# 1_8_4_-_-V2_0-2022_05_13.net
KiCad netlist of a schematic drawn in Altium Designer
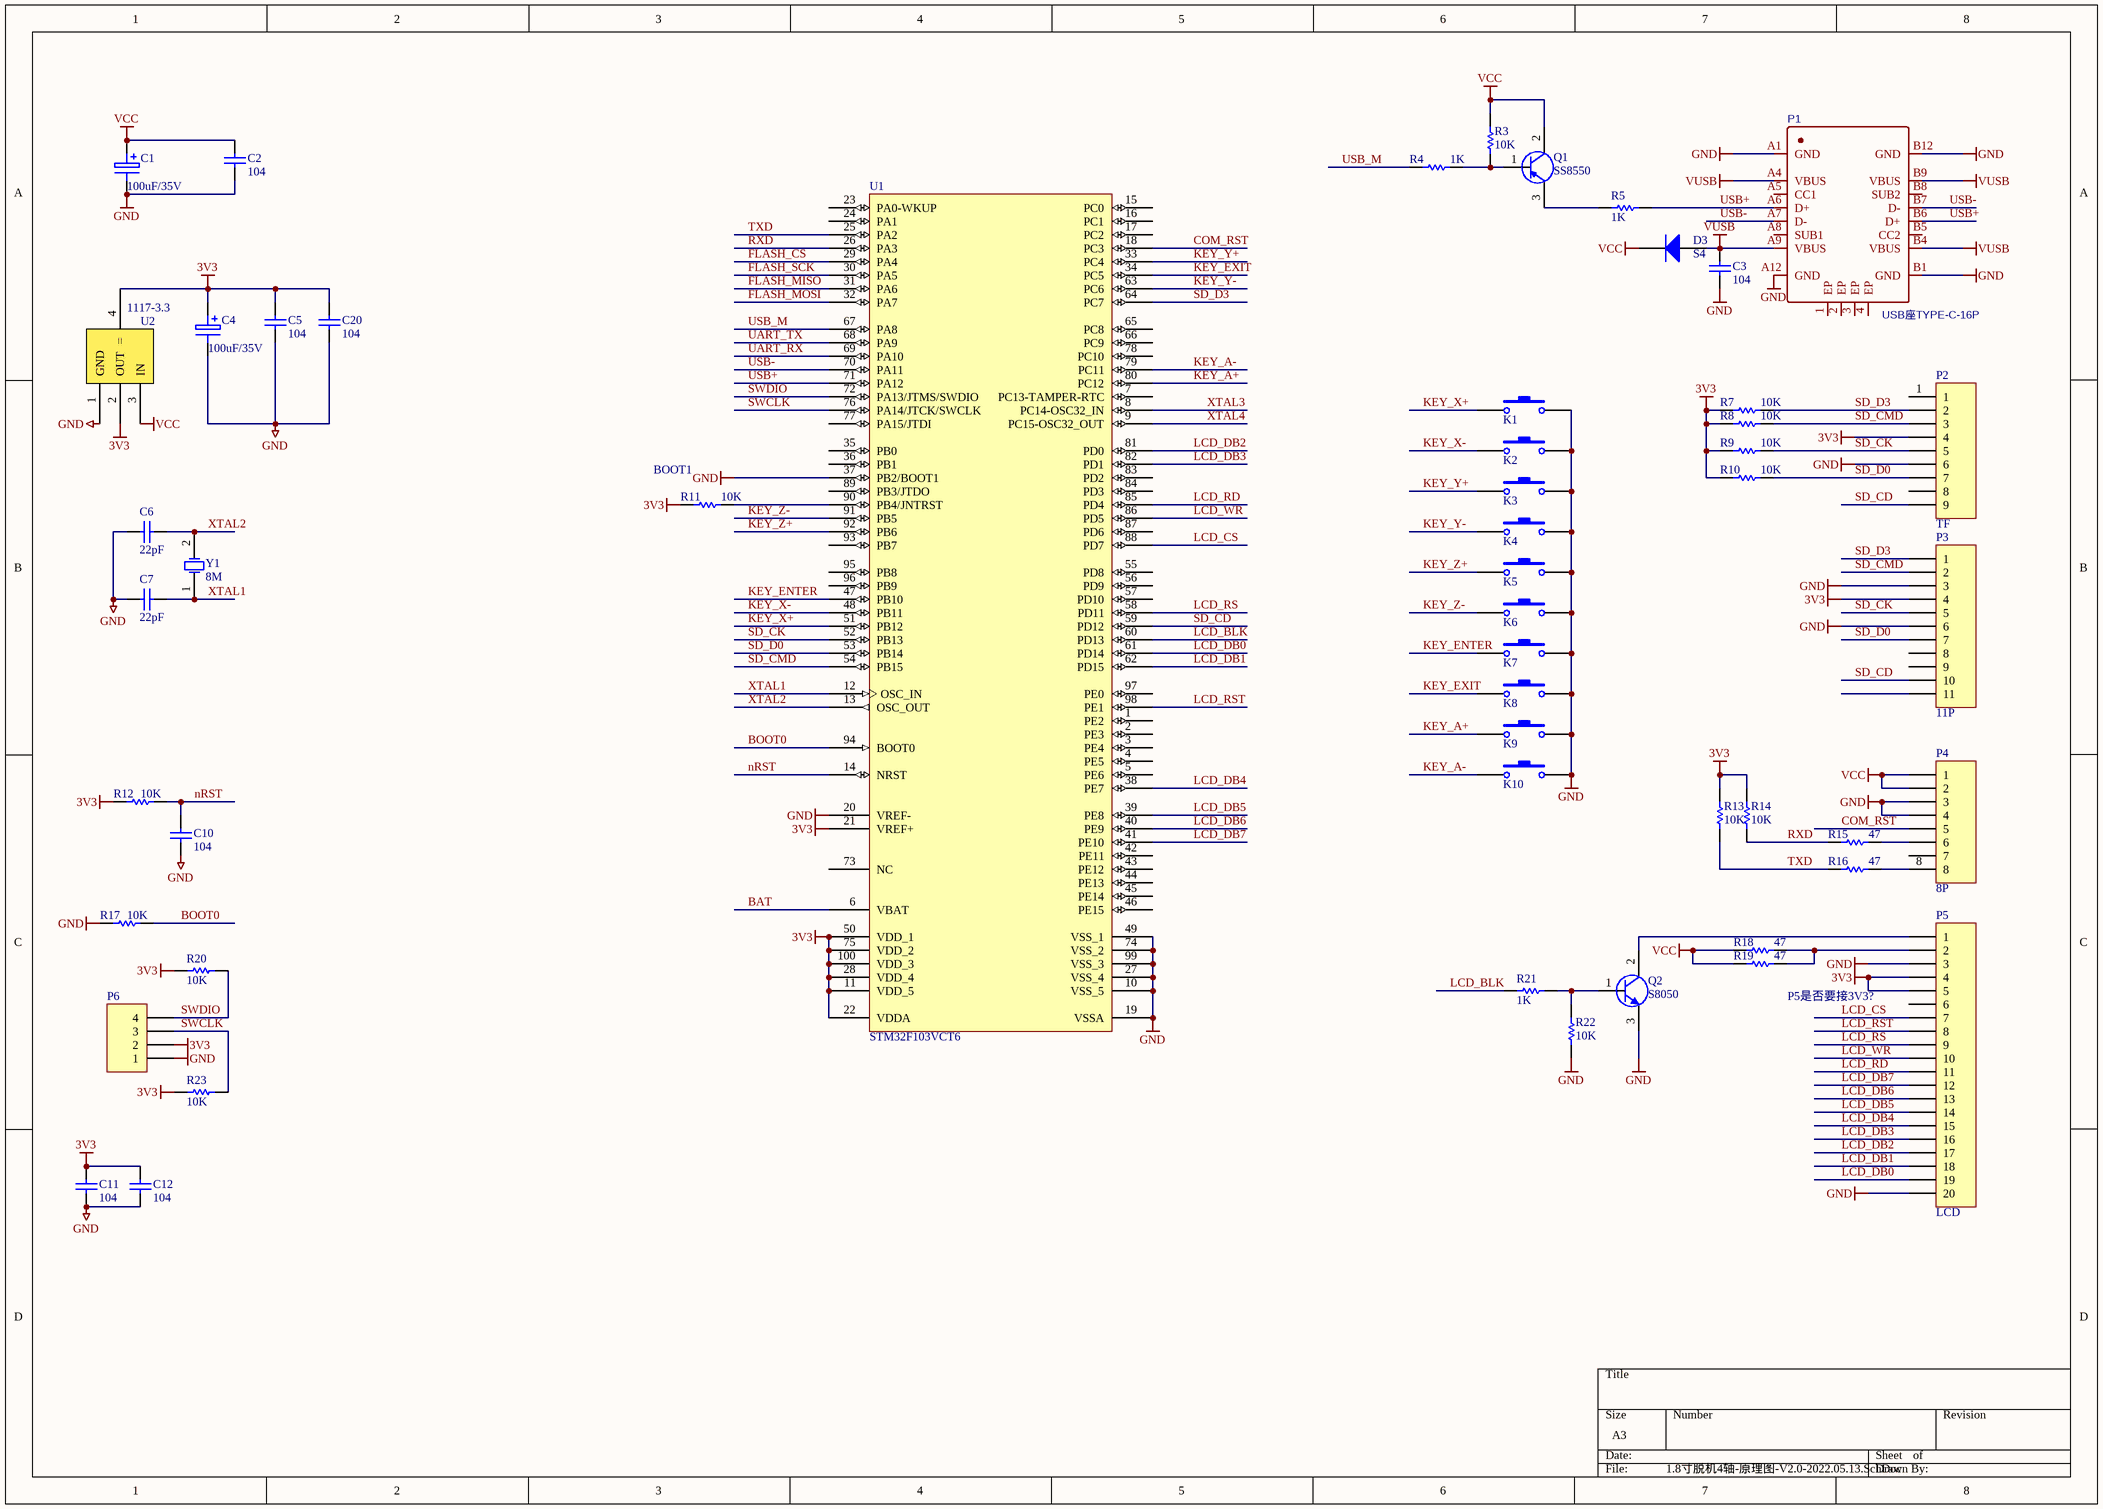
[diagram p0: 1.8寸脱机4轴-原理图-V2.0-2022.05.13.SchDoc]

(export (version "E")
  (design (tool "Eeschema 10.0.6"))
  (components
    (comp (ref "C1") (value "100uF/35V") (footprint "电解电容贴片6x6") (libsource (lib "*") (part "ELECTRO1")))
    (comp (ref "C2")
      (value "104")
      (footprint "0603C")
      (description "Capacitor (Semiconductor SIM Model)")
      (fields (field (name "PUBLISHER") "Altium Limited"))
      (libsource (lib "Miscellaneous Devices") (part "Cap Semi"))
    )
    (comp (ref "C3")
      (value "104")
      (footprint "0603C")
      (description "Capacitor (Semiconductor SIM Model)")
      (fields (field (name "PUBLISHER") "Altium Limited"))
      (libsource (lib "Miscellaneous Devices") (part "Cap Semi"))
    )
    (comp (ref "C4") (value "100uF/35V") (footprint "电解电容贴片6x6") (libsource (lib "*") (part "ELECTRO1")))
    (comp (ref "C5")
      (value "104")
      (footprint "0603C")
      (description "Capacitor (Semiconductor SIM Model)")
      (fields (field (name "PUBLISHER") "Altium Limited"))
      (libsource (lib "Miscellaneous Devices") (part "Cap Semi"))
    )
    (comp (ref "C6")
      (value "22pF")
      (footprint "0603C")
      (description "Capacitor (Semiconductor SIM Model)")
      (fields (field (name "PUBLISHER") "Altium Limited"))
      (libsource (lib "Miscellaneous Devices") (part "Cap Semi"))
    )
    (comp (ref "C7")
      (value "22pF")
      (footprint "0603C")
      (description "Capacitor (Semiconductor SIM Model)")
      (fields (field (name "PUBLISHER") "Altium Limited"))
      (libsource (lib "Miscellaneous Devices") (part "Cap Semi"))
    )
    (comp (ref "C10")
      (value "104")
      (footprint "0603C")
      (description "Capacitor (Semiconductor SIM Model)")
      (fields (field (name "PUBLISHER") "Altium Limited"))
      (libsource (lib "Miscellaneous Devices") (part "Cap Semi"))
    )
    (comp (ref "C11") (value "104") (footprint "0603C") (libsource (lib "SCH封装库") (part "CAP")))
    (comp (ref "C12") (value "104") (footprint "0603C") (libsource (lib "SCH封装库") (part "CAP")))
    (comp (ref "C20")
      (value "104")
      (footprint "0603C")
      (description "Capacitor (Semiconductor SIM Model)")
      (fields (field (name "Comment") "106") (field (name "PUBLISHER") "Altium Limited"))
      (libsource (lib "Miscellaneous Devices") (part "Cap Semi"))
    )
    (comp (ref "D3") (value "S4") (footprint "SOD-123") (libsource (lib "SCH封装库") (part "1N4148")))
    (comp (ref "K1") (value "~") (footprint "按键6x6贴片") (libsource (lib "SCH封装库") (part "按键")))
    (comp (ref "K2") (value "~") (footprint "按键6x6贴片") (libsource (lib "SCH封装库") (part "按键")))
    (comp (ref "K3") (value "~") (footprint "按键6x6贴片") (libsource (lib "SCH封装库") (part "按键")))
    (comp (ref "K4") (value "~") (footprint "按键6x6贴片") (libsource (lib "SCH封装库") (part "按键")))
    (comp (ref "K5") (value "~") (footprint "按键6x6贴片") (libsource (lib "SCH封装库") (part "按键")))
    (comp (ref "K6") (value "~") (footprint "按键6x6贴片") (libsource (lib "SCH封装库") (part "按键")))
    (comp (ref "K7") (value "~") (footprint "按键6x6贴片") (libsource (lib "SCH封装库") (part "按键")))
    (comp (ref "K8") (value "~") (footprint "按键6x6贴片") (libsource (lib "SCH封装库") (part "按键")))
    (comp (ref "K9") (value "~") (footprint "按键6x6贴片") (libsource (lib "SCH封装库") (part "按键")))
    (comp (ref "K10") (value "~") (footprint "按键6x6贴片") (libsource (lib "SCH封装库") (part "按键")))
    (comp (ref "P1")
      (value "USB座TYPE-C-16P")
      (footprint "USB-TYPE-C-16P-全贴片")
      (fields
        (field (name "BOM_SUPPLIER PART") "C709358")
        (field (name "BOM_MANUFACTURER PART") "KH-TYPE-C-16P-T")
        (field (name "CONTRIBUTOR") "LCSC")
      )
      (libsource (lib "SCH封装库") (part "USB座TYPE-C-16P"))
    )
    (comp (ref "P2") (value "TF") (footprint "TF卡自弹式") (libsource (lib "SCH封装库") (part "9P")))
    (comp (ref "P3") (value "11P") (footprint "SD卡座自弹式") (libsource (lib "SCH封装库") (part "11P")))
    (comp (ref "P4") (value "8P") (footprint "IDC8贴片") (libsource (lib "SCH封装库") (part "8P")))
    (comp (ref "P5") (value "LCD") (footprint "显示屏1.77寸") (libsource (lib "SCH封装库") (part "20P")))
    (comp (ref "P6") (value "~") (footprint "SIP4") (libsource (lib "SCH封装库") (part "4P")))
    (comp (ref "Q1") (value "SS8550") (footprint "SOT-23") (libsource (lib "SCH封装库") (part "PNP")))
    (comp (ref "Q2")
      (value "S8050")
      (footprint "SOT-23")
      (fields (field (name "PUBLISHER") "Altium Limited"))
      (libsource (lib "SCH封装库") (part "NPN"))
    )
    (comp (ref "R3")
      (value "10K")
      (footprint "0603R")
      (description "Resistor")
      (fields (field (name "PUBLISHER") "Altium Limited"))
      (libsource (lib "SCH封装库") (part "RES"))
    )
    (comp (ref "R4")
      (value "1K")
      (footprint "0603R")
      (description "Resistor")
      (fields (field (name "PUBLISHER") "Altium Limited"))
      (libsource (lib "SCH封装库") (part "RES"))
    )
    (comp (ref "R5")
      (value "1K")
      (footprint "0603R")
      (description "Resistor")
      (fields (field (name "PUBLISHER") "Altium Limited"))
      (libsource (lib "SCH封装库") (part "RES"))
    )
    (comp (ref "R7")
      (value "10K")
      (footprint "0603R")
      (description "Resistor")
      (fields (field (name "PUBLISHER") "Altium Limited"))
      (libsource (lib "SCH封装库") (part "RES"))
    )
    (comp (ref "R8")
      (value "10K")
      (footprint "0603R")
      (description "Resistor")
      (fields (field (name "PUBLISHER") "Altium Limited"))
      (libsource (lib "SCH封装库") (part "RES"))
    )
    (comp (ref "R9")
      (value "10K")
      (footprint "0603R")
      (description "Resistor")
      (fields (field (name "PUBLISHER") "Altium Limited"))
      (libsource (lib "SCH封装库") (part "RES"))
    )
    (comp (ref "R10")
      (value "10K")
      (footprint "0603R")
      (description "Resistor")
      (fields (field (name "PUBLISHER") "Altium Limited"))
      (libsource (lib "SCH封装库") (part "RES"))
    )
    (comp (ref "R11")
      (value "10K")
      (footprint "0603R")
      (description "Resistor")
      (fields (field (name "PUBLISHER") "Altium Limited"))
      (libsource (lib "SCH封装库") (part "RES"))
    )
    (comp (ref "R12")
      (value "10K")
      (footprint "0603R")
      (description "Resistor")
      (fields (field (name "Comment") "10k") (field (name "PUBLISHER") "Altium Limited"))
      (libsource (lib "SCH封装库") (part "RES"))
    )
    (comp (ref "R13")
      (value "10K")
      (footprint "0603R")
      (description "Resistor")
      (fields (field (name "PUBLISHER") "Altium Limited"))
      (libsource (lib "SCH封装库") (part "RES"))
    )
    (comp (ref "R14")
      (value "10K")
      (footprint "0603R")
      (description "Resistor")
      (fields (field (name "PUBLISHER") "Altium Limited"))
      (libsource (lib "SCH封装库") (part "RES"))
    )
    (comp (ref "R15")
      (value "47")
      (footprint "0603R")
      (description "Resistor")
      (fields (field (name "PUBLISHER") "Altium Limited"))
      (libsource (lib "SCH封装库") (part "RES"))
    )
    (comp (ref "R16")
      (value "47")
      (footprint "0603R")
      (description "Resistor")
      (fields (field (name "PUBLISHER") "Altium Limited"))
      (libsource (lib "SCH封装库") (part "RES"))
    )
    (comp (ref "R17")
      (value "10K")
      (footprint "0603R")
      (description "Resistor")
      (fields (field (name "Comment") "10k") (field (name "PUBLISHER") "Altium Limited"))
      (libsource (lib "SCH封装库") (part "RES"))
    )
    (comp (ref "R18")
      (value "47")
      (footprint "0603R")
      (description "Resistor")
      (fields (field (name "PUBLISHER") "Altium Limited"))
      (libsource (lib "SCH封装库") (part "RES"))
    )
    (comp (ref "R19")
      (value "47")
      (footprint "0603R")
      (description "Resistor")
      (fields (field (name "PUBLISHER") "Altium Limited"))
      (libsource (lib "SCH封装库") (part "RES"))
    )
    (comp (ref "R20")
      (value "10K")
      (footprint "0603R")
      (description "Resistor")
      (fields (field (name "Comment") "10k") (field (name "PUBLISHER") "Altium Limited"))
      (libsource (lib "SCH封装库") (part "RES"))
    )
    (comp (ref "R21")
      (value "1K")
      (footprint "0603R")
      (description "Resistor")
      (fields (field (name "PUBLISHER") "Altium Limited"))
      (libsource (lib "SCH封装库") (part "RES"))
    )
    (comp (ref "R22")
      (value "10K")
      (footprint "0603R")
      (description "Resistor")
      (fields (field (name "PUBLISHER") "Altium Limited"))
      (libsource (lib "SCH封装库") (part "RES"))
    )
    (comp (ref "R23")
      (value "10K")
      (footprint "0603R")
      (description "Resistor")
      (fields (field (name "Comment") "10k") (field (name "PUBLISHER") "Altium Limited"))
      (libsource (lib "SCH封装库") (part "RES"))
    )
    (comp (ref "U1")
      (value "STM32F103VCT6")
      (footprint "LQFP100")
      (description "STM32 ARM-based 32-bit MCU with 64 Kbytes Flash, 100-pin LQFP, Industrial Temperature")
      (fields (field (name "PUBLISHER") "*"))
      (libsource (lib "ST Microcontroller 32-Bit STM32 SCH") (part "STM32F103VBT6"))
    )
    (comp (ref "U2") (value "1117-3.3") (footprint "SOT-223") (libsource (lib "Party600") (part "LM1117")))
    (comp (ref "Y1")
      (value "8M")
      (footprint "晶振贴片")
      (description "Crystal Oscillator")
      (fields (field (name "PUBLISHER") "Altium Limited"))
      (libsource (lib "Miscellaneous Devices") (part "XTAL"))
    )
  )
  (nets
    (net (code "1") (name "/BAT") (class "Default")
      (node (ref "U1") (pin "6") (pinfunction "VBAT_6") (pintype "power_in"))
    )
    (net (code "2") (name "/BOOT0") (class "Default")
      (node (ref "R17") (pin "2") (pinfunction "2_2") (pintype "passive"))
      (node (ref "U1") (pin "94") (pinfunction "BOOT0_94") (pintype "input"))
    )
    (net (code "3") (name "/COM_RST") (class "Default")
      (node (ref "P4") (pin "5") (pinfunction "5_5") (pintype "passive"))
      (node (ref "U1") (pin "18") (pinfunction "PC3_18") (pintype "bidirectional"))
    )
    (net (code "4") (name "/FLASH_CS") (class "Default")
      (node (ref "U1") (pin "29") (pinfunction "PA4_29") (pintype "bidirectional"))
    )
    (net (code "5") (name "/FLASH_MISO") (class "Default")
      (node (ref "U1") (pin "31") (pinfunction "PA6_31") (pintype "bidirectional"))
    )
    (net (code "6") (name "/FLASH_MOSI") (class "Default")
      (node (ref "U1") (pin "32") (pinfunction "PA7_32") (pintype "bidirectional"))
    )
    (net (code "7") (name "/FLASH_SCK") (class "Default")
      (node (ref "U1") (pin "30") (pinfunction "PA5_30") (pintype "bidirectional"))
    )
    (net (code "8") (name "/KEY_A+") (class "Default")
      (node (ref "K9") (pin "1") (pinfunction "1_1") (pintype "passive"))
      (node (ref "U1") (pin "80") (pinfunction "PC12_80") (pintype "bidirectional"))
    )
    (net (code "9") (name "/KEY_A-") (class "Default")
      (node (ref "K10") (pin "1") (pinfunction "1_1") (pintype "passive"))
      (node (ref "U1") (pin "79") (pinfunction "PC11_79") (pintype "bidirectional"))
    )
    (net (code "10") (name "/KEY_ENTER") (class "Default")
      (node (ref "K7") (pin "1") (pinfunction "1_1") (pintype "passive"))
      (node (ref "U1") (pin "47") (pinfunction "PB10_47") (pintype "bidirectional"))
    )
    (net (code "11") (name "/KEY_EXIT") (class "Default")
      (node (ref "K8") (pin "1") (pinfunction "1_1") (pintype "passive"))
      (node (ref "U1") (pin "34") (pinfunction "PC5_34") (pintype "bidirectional"))
    )
    (net (code "12") (name "/KEY_X+") (class "Default")
      (node (ref "K1") (pin "1") (pinfunction "1_1") (pintype "passive"))
      (node (ref "U1") (pin "51") (pinfunction "PB12_51") (pintype "bidirectional"))
    )
    (net (code "13") (name "/KEY_X-") (class "Default")
      (node (ref "K2") (pin "1") (pinfunction "1_1") (pintype "passive"))
      (node (ref "U1") (pin "48") (pinfunction "PB11_48") (pintype "bidirectional"))
    )
    (net (code "14") (name "/KEY_Y+") (class "Default")
      (node (ref "K3") (pin "1") (pinfunction "1_1") (pintype "passive"))
      (node (ref "U1") (pin "33") (pinfunction "PC4_33") (pintype "bidirectional"))
    )
    (net (code "15") (name "/KEY_Y-") (class "Default")
      (node (ref "K4") (pin "1") (pinfunction "1_1") (pintype "passive"))
      (node (ref "U1") (pin "63") (pinfunction "PC6_63") (pintype "bidirectional"))
    )
    (net (code "16") (name "/KEY_Z+") (class "Default")
      (node (ref "K5") (pin "1") (pinfunction "1_1") (pintype "passive"))
      (node (ref "U1") (pin "92") (pinfunction "PB6_92") (pintype "bidirectional"))
    )
    (net (code "17") (name "/KEY_Z-") (class "Default")
      (node (ref "K6") (pin "1") (pinfunction "1_1") (pintype "passive"))
      (node (ref "U1") (pin "91") (pinfunction "PB5_91") (pintype "bidirectional"))
    )
    (net (code "18") (name "/LCD_BLK") (class "Default")
      (node (ref "R21") (pin "2") (pinfunction "2_2") (pintype "passive"))
      (node (ref "U1") (pin "60") (pinfunction "PD13_60") (pintype "bidirectional"))
    )
    (net (code "19") (name "/LCD_CS") (class "Default")
      (node (ref "P5") (pin "7") (pinfunction "7_7") (pintype "passive"))
      (node (ref "U1") (pin "88") (pinfunction "PD7_88") (pintype "bidirectional"))
    )
    (net (code "20") (name "/LCD_DB0") (class "Default")
      (node (ref "P5") (pin "19") (pinfunction "19_19") (pintype "passive"))
      (node (ref "U1") (pin "61") (pinfunction "PD14_61") (pintype "bidirectional"))
    )
    (net (code "21") (name "/LCD_DB1") (class "Default")
      (node (ref "P5") (pin "18") (pinfunction "18_18") (pintype "passive"))
      (node (ref "U1") (pin "62") (pinfunction "PD15_62") (pintype "bidirectional"))
    )
    (net (code "22") (name "/LCD_DB2") (class "Default")
      (node (ref "P5") (pin "17") (pinfunction "17_17") (pintype "passive"))
      (node (ref "U1") (pin "81") (pinfunction "PD0_81") (pintype "bidirectional"))
    )
    (net (code "23") (name "/LCD_DB3") (class "Default")
      (node (ref "P5") (pin "16") (pinfunction "16_16") (pintype "passive"))
      (node (ref "U1") (pin "82") (pinfunction "PD1_82") (pintype "bidirectional"))
    )
    (net (code "24") (name "/LCD_DB4") (class "Default")
      (node (ref "P5") (pin "15") (pinfunction "15_15") (pintype "passive"))
      (node (ref "U1") (pin "38") (pinfunction "PE7_38") (pintype "bidirectional"))
    )
    (net (code "25") (name "/LCD_DB5") (class "Default")
      (node (ref "P5") (pin "14") (pinfunction "14_14") (pintype "passive"))
      (node (ref "U1") (pin "39") (pinfunction "PE8_39") (pintype "bidirectional"))
    )
    (net (code "26") (name "/LCD_DB6") (class "Default")
      (node (ref "P5") (pin "13") (pinfunction "13_13") (pintype "passive"))
      (node (ref "U1") (pin "40") (pinfunction "PE9_40") (pintype "bidirectional"))
    )
    (net (code "27") (name "/LCD_DB7") (class "Default")
      (node (ref "P5") (pin "12") (pinfunction "12_12") (pintype "passive"))
      (node (ref "U1") (pin "41") (pinfunction "PE10_41") (pintype "bidirectional"))
    )
    (net (code "28") (name "/LCD_RD") (class "Default")
      (node (ref "P5") (pin "11") (pinfunction "11_11") (pintype "passive"))
      (node (ref "U1") (pin "85") (pinfunction "PD4_85") (pintype "bidirectional"))
    )
    (net (code "29") (name "/LCD_RS") (class "Default")
      (node (ref "P5") (pin "9") (pinfunction "9_9") (pintype "passive"))
      (node (ref "U1") (pin "58") (pinfunction "PD11_58") (pintype "bidirectional"))
    )
    (net (code "30") (name "/LCD_RST") (class "Default")
      (node (ref "P5") (pin "8") (pinfunction "8_8") (pintype "passive"))
      (node (ref "U1") (pin "98") (pinfunction "PE1_98") (pintype "bidirectional"))
    )
    (net (code "31") (name "/LCD_WR") (class "Default")
      (node (ref "P5") (pin "10") (pinfunction "10_10") (pintype "passive"))
      (node (ref "U1") (pin "86") (pinfunction "PD5_86") (pintype "bidirectional"))
    )
    (net (code "32") (name "/RXD") (class "Default")
      (node (ref "R14") (pin "1") (pinfunction "1_1") (pintype "passive"))
      (node (ref "R15") (pin "1") (pinfunction "1_1") (pintype "passive"))
      (node (ref "U1") (pin "26") (pinfunction "PA3_26") (pintype "bidirectional"))
    )
    (net (code "33") (name "/SD_CD") (class "Default")
      (node (ref "P2") (pin "9") (pinfunction "9_9") (pintype "passive"))
      (node (ref "P3") (pin "10") (pinfunction "10_10") (pintype "passive"))
      (node (ref "U1") (pin "59") (pinfunction "PD12_59") (pintype "bidirectional"))
    )
    (net (code "34") (name "/SD_CK") (class "Default")
      (node (ref "P2") (pin "5") (pinfunction "5_5") (pintype "passive"))
      (node (ref "P3") (pin "5") (pinfunction "5_5") (pintype "passive"))
      (node (ref "R9") (pin "2") (pinfunction "2_2") (pintype "passive"))
      (node (ref "U1") (pin "52") (pinfunction "PB13_52") (pintype "bidirectional"))
    )
    (net (code "35") (name "/SD_CMD") (class "Default")
      (node (ref "P2") (pin "3") (pinfunction "3_3") (pintype "passive"))
      (node (ref "P3") (pin "2") (pinfunction "2_2") (pintype "passive"))
      (node (ref "R8") (pin "2") (pinfunction "2_2") (pintype "passive"))
      (node (ref "U1") (pin "54") (pinfunction "PB15_54") (pintype "bidirectional"))
    )
    (net (code "36") (name "/SD_D0") (class "Default")
      (node (ref "P2") (pin "7") (pinfunction "7_7") (pintype "passive"))
      (node (ref "P3") (pin "7") (pinfunction "7_7") (pintype "passive"))
      (node (ref "R10") (pin "2") (pinfunction "2_2") (pintype "passive"))
      (node (ref "U1") (pin "53") (pinfunction "PB14_53") (pintype "bidirectional"))
    )
    (net (code "37") (name "/SD_D3") (class "Default")
      (node (ref "P2") (pin "2") (pinfunction "2_2") (pintype "passive"))
      (node (ref "P3") (pin "1") (pinfunction "1_1") (pintype "passive"))
      (node (ref "R7") (pin "2") (pinfunction "2_2") (pintype "passive"))
      (node (ref "U1") (pin "64") (pinfunction "PC7_64") (pintype "bidirectional"))
    )
    (net (code "38") (name "/SWCLK") (class "Default")
      (node (ref "P6") (pin "3") (pinfunction "3_3") (pintype "passive"))
      (node (ref "R23") (pin "1") (pinfunction "1_1") (pintype "passive"))
      (node (ref "U1") (pin "76") (pinfunction "PA14/JTCK/SWCLK_76") (pintype "bidirectional"))
    )
    (net (code "39") (name "/SWDIO") (class "Default")
      (node (ref "P6") (pin "4") (pinfunction "4_4") (pintype "passive"))
      (node (ref "R20") (pin "1") (pinfunction "1_1") (pintype "passive"))
      (node (ref "U1") (pin "72") (pinfunction "PA13/JTMS/SWDIO_72") (pintype "bidirectional"))
    )
    (net (code "40") (name "/TXD") (class "Default")
      (node (ref "R13") (pin "1") (pinfunction "1_1") (pintype "passive"))
      (node (ref "R16") (pin "1") (pinfunction "1_1") (pintype "passive"))
      (node (ref "U1") (pin "25") (pinfunction "PA2_25") (pintype "bidirectional"))
    )
    (net (code "41") (name "/UART_RX") (class "Default")
      (node (ref "U1") (pin "69") (pinfunction "PA10_69") (pintype "bidirectional"))
    )
    (net (code "42") (name "/UART_TX") (class "Default")
      (node (ref "U1") (pin "68") (pinfunction "PA9_68") (pintype "bidirectional"))
    )
    (net (code "43") (name "/USB+") (class "Default")
      (node (ref "P1") (pin "A6") (pinfunction "D+_A6") (pintype "passive"))
      (node (ref "P1") (pin "B6") (pinfunction "D+_B6") (pintype "passive"))
      (node (ref "R5") (pin "2") (pinfunction "2_2") (pintype "passive"))
      (node (ref "U1") (pin "71") (pinfunction "PA12_71") (pintype "bidirectional"))
    )
    (net (code "44") (name "/USB-") (class "Default")
      (node (ref "P1") (pin "A7") (pinfunction "D-_A7") (pintype "passive"))
      (node (ref "P1") (pin "B7") (pinfunction "D-_B7") (pintype "passive"))
      (node (ref "U1") (pin "70") (pinfunction "PA11_70") (pintype "bidirectional"))
    )
    (net (code "45") (name "/USB_M") (class "Default")
      (node (ref "R4") (pin "2") (pinfunction "2_2") (pintype "passive"))
      (node (ref "U1") (pin "67") (pinfunction "PA8_67") (pintype "bidirectional"))
    )
    (net (code "46") (name "/XTAL1") (class "Default")
      (node (ref "C7") (pin "1") (pinfunction "1_1") (pintype "passive"))
      (node (ref "U1") (pin "12") (pinfunction "OSC_IN_12") (pintype "input"))
      (node (ref "Y1") (pin "1") (pinfunction "OSC1_1") (pintype "passive"))
    )
    (net (code "47") (name "/XTAL2") (class "Default")
      (node (ref "C6") (pin "1") (pinfunction "1_1") (pintype "passive"))
      (node (ref "U1") (pin "13") (pinfunction "OSC_OUT_13") (pintype "output"))
      (node (ref "Y1") (pin "2") (pinfunction "OSC2_2") (pintype "passive"))
    )
    (net (code "48") (name "/XTAL3") (class "Default")
      (node (ref "U1") (pin "8") (pinfunction "PC14-OSC32_IN_8") (pintype "bidirectional"))
    )
    (net (code "49") (name "/XTAL4") (class "Default")
      (node (ref "U1") (pin "9") (pinfunction "PC15-OSC32_OUT_9") (pintype "bidirectional"))
    )
    (net (code "50") (name "/nRST") (class "Default")
      (node (ref "C10") (pin "2") (pinfunction "2_2") (pintype "passive"))
      (node (ref "R12") (pin "2") (pinfunction "2_2") (pintype "passive"))
      (node (ref "U1") (pin "14") (pinfunction "NRST_14") (pintype "bidirectional"))
    )
    (net (code "51") (name "3V3") (class "Default")
      (node (ref "C11") (pin "2") (pinfunction "2_2") (pintype "passive"))
      (node (ref "C12") (pin "2") (pinfunction "2_2") (pintype "passive"))
      (node (ref "C20") (pin "2") (pinfunction "2_2") (pintype "passive"))
      (node (ref "C4") (pin "1") (pintype "passive"))
      (node (ref "C5") (pin "2") (pinfunction "2_2") (pintype "passive"))
      (node (ref "P2") (pin "4") (pinfunction "4_4") (pintype "passive"))
      (node (ref "P3") (pin "4") (pinfunction "4_4") (pintype "passive"))
      (node (ref "P5") (pin "4") (pinfunction "4_4") (pintype "passive"))
      (node (ref "P5") (pin "5") (pinfunction "5_5") (pintype "passive"))
      (node (ref "P6") (pin "2") (pinfunction "2_2") (pintype "passive"))
      (node (ref "R10") (pin "1") (pinfunction "1_1") (pintype "passive"))
      (node (ref "R11") (pin "1") (pinfunction "1_1") (pintype "passive"))
      (node (ref "R12") (pin "1") (pinfunction "1_1") (pintype "passive"))
      (node (ref "R13") (pin "2") (pinfunction "2_2") (pintype "passive"))
      (node (ref "R14") (pin "2") (pinfunction "2_2") (pintype "passive"))
      (node (ref "R20") (pin "2") (pinfunction "2_2") (pintype "passive"))
      (node (ref "R23") (pin "2") (pinfunction "2_2") (pintype "passive"))
      (node (ref "R7") (pin "1") (pinfunction "1_1") (pintype "passive"))
      (node (ref "R8") (pin "1") (pinfunction "1_1") (pintype "passive"))
      (node (ref "R9") (pin "1") (pinfunction "1_1") (pintype "passive"))
      (node (ref "U1") (pin "100") (pinfunction "VDD_3_100") (pintype "power_in"))
      (node (ref "U1") (pin "11") (pinfunction "VDD_5_11") (pintype "power_in"))
      (node (ref "U1") (pin "21") (pinfunction "VREF+_21") (pintype "power_in"))
      (node (ref "U1") (pin "22") (pinfunction "VDDA_22") (pintype "power_in"))
      (node (ref "U1") (pin "28") (pinfunction "VDD_4_28") (pintype "power_in"))
      (node (ref "U1") (pin "50") (pinfunction "VDD_1_50") (pintype "power_in"))
      (node (ref "U1") (pin "75") (pinfunction "VDD_2_75") (pintype "power_in"))
      (node (ref "U2") (pin "2") (pinfunction "OUT_2") (pintype "power_in"))
      (node (ref "U2") (pin "4") (pinfunction "=_4") (pintype "power_in"))
    )
    (net (code "52") (name "GND") (class "Default")
      (node (ref "C1") (pin "2") (pintype "passive"))
      (node (ref "C10") (pin "1") (pinfunction "1_1") (pintype "passive"))
      (node (ref "C11") (pin "1") (pinfunction "1_1") (pintype "passive"))
      (node (ref "C12") (pin "1") (pinfunction "1_1") (pintype "passive"))
      (node (ref "C2") (pin "1") (pinfunction "1_1") (pintype "passive"))
      (node (ref "C20") (pin "1") (pinfunction "1_1") (pintype "passive"))
      (node (ref "C3") (pin "1") (pinfunction "1_1") (pintype "passive"))
      (node (ref "C4") (pin "2") (pintype "passive"))
      (node (ref "C5") (pin "1") (pinfunction "1_1") (pintype "passive"))
      (node (ref "C6") (pin "2") (pinfunction "2_2") (pintype "passive"))
      (node (ref "C7") (pin "2") (pinfunction "2_2") (pintype "passive"))
      (node (ref "K1") (pin "2") (pinfunction "2_2") (pintype "passive"))
      (node (ref "K10") (pin "2") (pinfunction "2_2") (pintype "passive"))
      (node (ref "K2") (pin "2") (pinfunction "2_2") (pintype "passive"))
      (node (ref "K3") (pin "2") (pinfunction "2_2") (pintype "passive"))
      (node (ref "K4") (pin "2") (pinfunction "2_2") (pintype "passive"))
      (node (ref "K5") (pin "2") (pinfunction "2_2") (pintype "passive"))
      (node (ref "K6") (pin "2") (pinfunction "2_2") (pintype "passive"))
      (node (ref "K7") (pin "2") (pinfunction "2_2") (pintype "passive"))
      (node (ref "K8") (pin "2") (pinfunction "2_2") (pintype "passive"))
      (node (ref "K9") (pin "2") (pinfunction "2_2") (pintype "passive"))
      (node (ref "P1") (pin "A1") (pinfunction "GND_A1") (pintype "passive"))
      (node (ref "P1") (pin "A12") (pinfunction "GND_A12") (pintype "passive"))
      (node (ref "P1") (pin "B1") (pinfunction "GND_B1") (pintype "passive"))
      (node (ref "P1") (pin "B12") (pinfunction "GND_B12") (pintype "passive"))
      (node (ref "P2") (pin "6") (pinfunction "6_6") (pintype "passive"))
      (node (ref "P3") (pin "3") (pinfunction "3_3") (pintype "passive"))
      (node (ref "P3") (pin "6") (pinfunction "6_6") (pintype "passive"))
      (node (ref "P4") (pin "3") (pinfunction "3_3") (pintype "passive"))
      (node (ref "P4") (pin "4") (pinfunction "4_4") (pintype "passive"))
      (node (ref "P5") (pin "20") (pinfunction "20_20") (pintype "passive"))
      (node (ref "P5") (pin "3") (pinfunction "3_3") (pintype "passive"))
      (node (ref "P6") (pin "1") (pinfunction "1_1") (pintype "passive"))
      (node (ref "Q2") (pin "3") (pinfunction "E_3") (pintype "passive"))
      (node (ref "R17") (pin "1") (pinfunction "1_1") (pintype "passive"))
      (node (ref "R22") (pin "1") (pinfunction "1_1") (pintype "passive"))
      (node (ref "U1") (pin "10") (pinfunction "VSS_5_10") (pintype "power_in"))
      (node (ref "U1") (pin "19") (pinfunction "VSSA_19") (pintype "power_in"))
      (node (ref "U1") (pin "20") (pinfunction "VREF-_20") (pintype "power_in"))
      (node (ref "U1") (pin "27") (pinfunction "VSS_4_27") (pintype "power_in"))
      (node (ref "U1") (pin "37") (pinfunction "PB2/BOOT1_37") (pintype "bidirectional"))
      (node (ref "U1") (pin "49") (pinfunction "VSS_1_49") (pintype "power_in"))
      (node (ref "U1") (pin "74") (pinfunction "VSS_2_74") (pintype "power_in"))
      (node (ref "U1") (pin "99") (pinfunction "VSS_3_99") (pintype "power_in"))
      (node (ref "U2") (pin "1") (pinfunction "GND_1") (pintype "power_in"))
    )
    (net (code "53") (name "Net-(P4-Pad6)") (class "Default")
      (node (ref "P4") (pin "6") (pinfunction "6_6") (pintype "passive"))
      (node (ref "R15") (pin "2") (pinfunction "2_2") (pintype "passive"))
    )
    (net (code "54") (name "Net-(P4-Pad8)") (class "Default")
      (node (ref "P4") (pin "8") (pinfunction "8_8") (pintype "passive"))
      (node (ref "R16") (pin "2") (pinfunction "2_2") (pintype "passive"))
    )
    (net (code "55") (name "Net-(P5-Pad2)") (class "Default")
      (node (ref "P5") (pin "2") (pinfunction "2_2") (pintype "passive"))
      (node (ref "R18") (pin "1") (pinfunction "1_1") (pintype "passive"))
      (node (ref "R19") (pin "1") (pinfunction "1_1") (pintype "passive"))
    )
    (net (code "56") (name "Net-(Q1-B)") (class "Default")
      (node (ref "Q1") (pin "1") (pinfunction "B_1") (pintype "passive"))
      (node (ref "R3") (pin "2") (pinfunction "2_2") (pintype "passive"))
      (node (ref "R4") (pin "1") (pinfunction "1_1") (pintype "passive"))
    )
    (net (code "57") (name "Net-(Q1-E)") (class "Default")
      (node (ref "Q1") (pin "3") (pinfunction "E_3") (pintype "passive"))
      (node (ref "R5") (pin "1") (pinfunction "1_1") (pintype "passive"))
    )
    (net (code "58") (name "Net-(Q2-B)") (class "Default")
      (node (ref "Q2") (pin "1") (pinfunction "B_1") (pintype "passive"))
      (node (ref "R21") (pin "1") (pinfunction "1_1") (pintype "passive"))
      (node (ref "R22") (pin "2") (pinfunction "2_2") (pintype "passive"))
    )
    (net (code "59") (name "Net-(Q2-C)") (class "Default")
      (node (ref "P5") (pin "1") (pinfunction "1_1") (pintype "passive"))
      (node (ref "Q2") (pin "2") (pinfunction "C_2") (pintype "passive"))
    )
    (net (code "60") (name "Net-(U1-PB4{slash}JNTRST)") (class "Default")
      (node (ref "R11") (pin "2") (pinfunction "2_2") (pintype "passive"))
      (node (ref "U1") (pin "90") (pinfunction "PB4/JNTRST_90") (pintype "bidirectional"))
    )
    (net (code "61") (name "VCC") (class "Default")
      (node (ref "C1") (pin "1") (pintype "passive"))
      (node (ref "C2") (pin "2") (pinfunction "2_2") (pintype "passive"))
      (node (ref "D3") (pin "2") (pinfunction "2_2") (pintype "passive"))
      (node (ref "P4") (pin "1") (pinfunction "1_1") (pintype "passive"))
      (node (ref "P4") (pin "2") (pinfunction "2_2") (pintype "passive"))
      (node (ref "Q1") (pin "2") (pinfunction "C_2") (pintype "passive"))
      (node (ref "R18") (pin "2") (pinfunction "2_2") (pintype "passive"))
      (node (ref "R19") (pin "2") (pinfunction "2_2") (pintype "passive"))
      (node (ref "R3") (pin "1") (pinfunction "1_1") (pintype "passive"))
      (node (ref "U2") (pin "3") (pinfunction "IN_3") (pintype "power_in"))
    )
    (net (code "62") (name "VUSB") (class "Default")
      (node (ref "C3") (pin "2") (pinfunction "2_2") (pintype "passive"))
      (node (ref "D3") (pin "1") (pinfunction "1_1") (pintype "passive"))
      (node (ref "P1") (pin "A4") (pinfunction "VBUS_A4") (pintype "passive"))
      (node (ref "P1") (pin "A9") (pinfunction "VBUS_A9") (pintype "passive"))
      (node (ref "P1") (pin "B4") (pinfunction "VBUS_B4") (pintype "passive"))
      (node (ref "P1") (pin "B9") (pinfunction "VBUS_B9") (pintype "passive"))
    )
    (net (code "63") (name "unconnected-(P1-CC1-PadA5)") (class "Default")
      (node (ref "P1") (pin "A5") (pinfunction "CC1_A5") (pintype "passive"))
    )
    (net (code "64") (name "unconnected-(P1-CC2-PadB5)") (class "Default")
      (node (ref "P1") (pin "B5") (pinfunction "CC2_B5") (pintype "passive"))
    )
    (net (code "65") (name "unconnected-(P1-EP-Pad1)") (class "Default")
      (node (ref "P1") (pin "1") (pinfunction "EP_1") (pintype "passive"))
    )
    (net (code "66") (name "unconnected-(P1-EP-Pad2)") (class "Default")
      (node (ref "P1") (pin "2") (pinfunction "EP_2") (pintype "passive"))
    )
    (net (code "67") (name "unconnected-(P1-EP-Pad3)") (class "Default")
      (node (ref "P1") (pin "3") (pinfunction "EP_3") (pintype "passive"))
    )
    (net (code "68") (name "unconnected-(P1-EP-Pad4)") (class "Default")
      (node (ref "P1") (pin "4") (pinfunction "EP_4") (pintype "passive"))
    )
    (net (code "69") (name "unconnected-(P1-SUB1-PadA8)") (class "Default")
      (node (ref "P1") (pin "A8") (pinfunction "SUB1_A8") (pintype "passive"))
    )
    (net (code "70") (name "unconnected-(P1-SUB2-PadB8)") (class "Default")
      (node (ref "P1") (pin "B8") (pinfunction "SUB2_B8") (pintype "passive"))
    )
    (net (code "71") (name "unconnected-(P2-Pad1)") (class "Default")
      (node (ref "P2") (pin "1") (pinfunction "1_1") (pintype "passive"))
    )
    (net (code "72") (name "unconnected-(P2-Pad8)") (class "Default")
      (node (ref "P2") (pin "8") (pinfunction "8_8") (pintype "passive"))
    )
    (net (code "73") (name "unconnected-(P3-Pad8)") (class "Default")
      (node (ref "P3") (pin "8") (pinfunction "8_8") (pintype "passive"))
    )
    (net (code "74") (name "unconnected-(P3-Pad9)") (class "Default")
      (node (ref "P3") (pin "9") (pinfunction "9_9") (pintype "passive"))
    )
    (net (code "75") (name "unconnected-(P3-Pad11)") (class "Default")
      (node (ref "P3") (pin "11") (pinfunction "11_11") (pintype "passive"))
    )
    (net (code "76") (name "unconnected-(P4-Pad7)") (class "Default")
      (node (ref "P4") (pin "7") (pinfunction "7_7") (pintype "passive"))
    )
    (net (code "77") (name "unconnected-(P5-Pad6)") (class "Default")
      (node (ref "P5") (pin "6") (pinfunction "6_6") (pintype "passive"))
    )
    (net (code "78") (name "unconnected-(U1-NC-Pad73)") (class "Default")
      (node (ref "U1") (pin "73") (pinfunction "NC_73") (pintype "passive"))
    )
    (net (code "79") (name "unconnected-(U1-PA0-WKUP-Pad23)") (class "Default")
      (node (ref "U1") (pin "23") (pinfunction "PA0-WKUP_23") (pintype "bidirectional"))
    )
    (net (code "80") (name "unconnected-(U1-PA1-Pad24)") (class "Default")
      (node (ref "U1") (pin "24") (pinfunction "PA1_24") (pintype "bidirectional"))
    )
    (net (code "81") (name "unconnected-(U1-PA15{slash}JTDI-Pad77)") (class "Default")
      (node (ref "U1") (pin "77") (pinfunction "PA15/JTDI_77") (pintype "bidirectional"))
    )
    (net (code "82") (name "unconnected-(U1-PB0-Pad35)") (class "Default")
      (node (ref "U1") (pin "35") (pinfunction "PB0_35") (pintype "bidirectional"))
    )
    (net (code "83") (name "unconnected-(U1-PB1-Pad36)") (class "Default")
      (node (ref "U1") (pin "36") (pinfunction "PB1_36") (pintype "bidirectional"))
    )
    (net (code "84") (name "unconnected-(U1-PB3{slash}JTDO-Pad89)") (class "Default")
      (node (ref "U1") (pin "89") (pinfunction "PB3/JTDO_89") (pintype "bidirectional"))
    )
    (net (code "85") (name "unconnected-(U1-PB7-Pad93)") (class "Default")
      (node (ref "U1") (pin "93") (pinfunction "PB7_93") (pintype "bidirectional"))
    )
    (net (code "86") (name "unconnected-(U1-PB8-Pad95)") (class "Default")
      (node (ref "U1") (pin "95") (pinfunction "PB8_95") (pintype "bidirectional"))
    )
    (net (code "87") (name "unconnected-(U1-PB9-Pad96)") (class "Default")
      (node (ref "U1") (pin "96") (pinfunction "PB9_96") (pintype "bidirectional"))
    )
    (net (code "88") (name "unconnected-(U1-PC0-Pad15)") (class "Default")
      (node (ref "U1") (pin "15") (pinfunction "PC0_15") (pintype "bidirectional"))
    )
    (net (code "89") (name "unconnected-(U1-PC1-Pad16)") (class "Default")
      (node (ref "U1") (pin "16") (pinfunction "PC1_16") (pintype "bidirectional"))
    )
    (net (code "90") (name "unconnected-(U1-PC2-Pad17)") (class "Default")
      (node (ref "U1") (pin "17") (pinfunction "PC2_17") (pintype "bidirectional"))
    )
    (net (code "91") (name "unconnected-(U1-PC8-Pad65)") (class "Default")
      (node (ref "U1") (pin "65") (pinfunction "PC8_65") (pintype "bidirectional"))
    )
    (net (code "92") (name "unconnected-(U1-PC9-Pad66)") (class "Default")
      (node (ref "U1") (pin "66") (pinfunction "PC9_66") (pintype "bidirectional"))
    )
    (net (code "93") (name "unconnected-(U1-PC10-Pad78)") (class "Default")
      (node (ref "U1") (pin "78") (pinfunction "PC10_78") (pintype "bidirectional"))
    )
    (net (code "94") (name "unconnected-(U1-PC13-TAMPER-RTC-Pad7)") (class "Default")
      (node (ref "U1") (pin "7") (pinfunction "PC13-TAMPER-RTC_7") (pintype "bidirectional"))
    )
    (net (code "95") (name "unconnected-(U1-PD2-Pad83)") (class "Default")
      (node (ref "U1") (pin "83") (pinfunction "PD2_83") (pintype "bidirectional"))
    )
    (net (code "96") (name "unconnected-(U1-PD3-Pad84)") (class "Default")
      (node (ref "U1") (pin "84") (pinfunction "PD3_84") (pintype "bidirectional"))
    )
    (net (code "97") (name "unconnected-(U1-PD6-Pad87)") (class "Default")
      (node (ref "U1") (pin "87") (pinfunction "PD6_87") (pintype "bidirectional"))
    )
    (net (code "98") (name "unconnected-(U1-PD8-Pad55)") (class "Default")
      (node (ref "U1") (pin "55") (pinfunction "PD8_55") (pintype "bidirectional"))
    )
    (net (code "99") (name "unconnected-(U1-PD9-Pad56)") (class "Default")
      (node (ref "U1") (pin "56") (pinfunction "PD9_56") (pintype "bidirectional"))
    )
    (net (code "100") (name "unconnected-(U1-PD10-Pad57)") (class "Default")
      (node (ref "U1") (pin "57") (pinfunction "PD10_57") (pintype "bidirectional"))
    )
    (net (code "101") (name "unconnected-(U1-PE0-Pad97)") (class "Default")
      (node (ref "U1") (pin "97") (pinfunction "PE0_97") (pintype "bidirectional"))
    )
    (net (code "102") (name "unconnected-(U1-PE2-Pad1)") (class "Default")
      (node (ref "U1") (pin "1") (pinfunction "PE2_1") (pintype "bidirectional"))
    )
    (net (code "103") (name "unconnected-(U1-PE3-Pad2)") (class "Default")
      (node (ref "U1") (pin "2") (pinfunction "PE3_2") (pintype "bidirectional"))
    )
    (net (code "104") (name "unconnected-(U1-PE4-Pad3)") (class "Default")
      (node (ref "U1") (pin "3") (pinfunction "PE4_3") (pintype "bidirectional"))
    )
    (net (code "105") (name "unconnected-(U1-PE5-Pad4)") (class "Default")
      (node (ref "U1") (pin "4") (pinfunction "PE5_4") (pintype "bidirectional"))
    )
    (net (code "106") (name "unconnected-(U1-PE6-Pad5)") (class "Default")
      (node (ref "U1") (pin "5") (pinfunction "PE6_5") (pintype "bidirectional"))
    )
    (net (code "107") (name "unconnected-(U1-PE11-Pad42)") (class "Default")
      (node (ref "U1") (pin "42") (pinfunction "PE11_42") (pintype "bidirectional"))
    )
    (net (code "108") (name "unconnected-(U1-PE12-Pad43)") (class "Default")
      (node (ref "U1") (pin "43") (pinfunction "PE12_43") (pintype "bidirectional"))
    )
    (net (code "109") (name "unconnected-(U1-PE13-Pad44)") (class "Default")
      (node (ref "U1") (pin "44") (pinfunction "PE13_44") (pintype "bidirectional"))
    )
    (net (code "110") (name "unconnected-(U1-PE14-Pad45)") (class "Default")
      (node (ref "U1") (pin "45") (pinfunction "PE14_45") (pintype "bidirectional"))
    )
    (net (code "111") (name "unconnected-(U1-PE15-Pad46)") (class "Default")
      (node (ref "U1") (pin "46") (pinfunction "PE15_46") (pintype "bidirectional"))
    )
  )
)
